# EFM_Power.net
KiCad netlist of a schematic drawn in Altium Designer
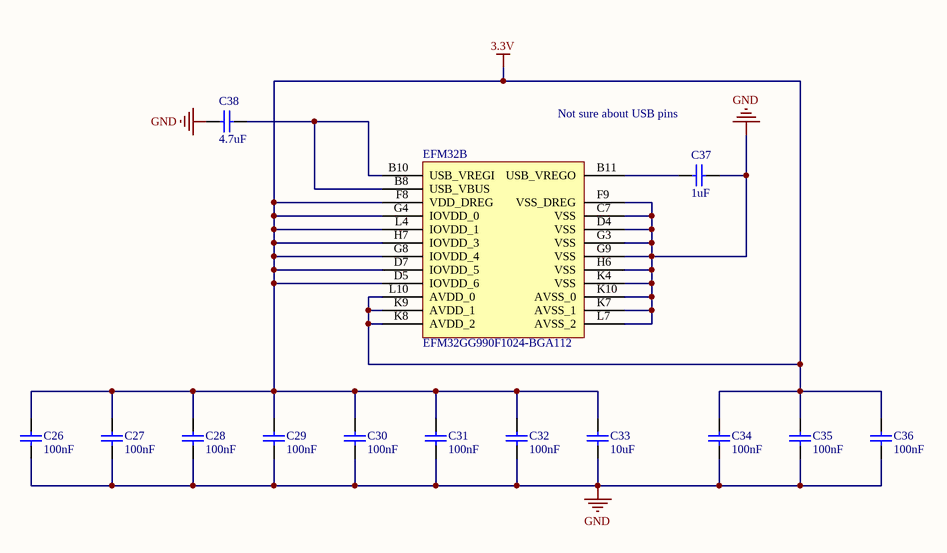
[diagram p0: EFM Power.SchDoc]

(export (version "E")
  (design (tool "Eeschema 10.0.6"))
  (components
    (comp (ref "C26")
      (value "100nF")
      (footprint "CAPC0603(1608)100_N")
      (description "CAP 0.5pF 10V Â±0.1pF 0603 (1608 Metric) Thickness 1mm SMD")
      (fields (field (name "TOLERANCE") "Â±0.1pF"))
      (libsource (lib "Altium Inc") (part "CMP-1035-00001-1"))
    )
    (comp (ref "C27")
      (value "100nF")
      (footprint "CAPC0603(1608)100_N")
      (description "CAP 0.5pF 10V Â±0.1pF 0603 (1608 Metric) Thickness 1mm SMD")
      (fields (field (name "TOLERANCE") "Â±0.1pF"))
      (libsource (lib "Altium Inc") (part "CMP-1035-00001-1"))
    )
    (comp (ref "C28")
      (value "100nF")
      (footprint "CAPC0603(1608)100_N")
      (description "CAP 0.5pF 10V Â±0.1pF 0603 (1608 Metric) Thickness 1mm SMD")
      (fields (field (name "TOLERANCE") "Â±0.1pF"))
      (libsource (lib "Altium Inc") (part "CMP-1035-00001-1"))
    )
    (comp (ref "C29")
      (value "100nF")
      (footprint "CAPC0603(1608)100_N")
      (description "CAP 0.5pF 10V Â±0.1pF 0603 (1608 Metric) Thickness 1mm SMD")
      (fields (field (name "TOLERANCE") "Â±0.1pF"))
      (libsource (lib "Altium Inc") (part "CMP-1035-00001-1"))
    )
    (comp (ref "C30")
      (value "100nF")
      (footprint "CAPC0603(1608)100_N")
      (description "CAP 0.5pF 10V Â±0.1pF 0603 (1608 Metric) Thickness 1mm SMD")
      (fields (field (name "TOLERANCE") "Â±0.1pF"))
      (libsource (lib "Altium Inc") (part "CMP-1035-00001-1"))
    )
    (comp (ref "C31")
      (value "100nF")
      (footprint "CAPC0603(1608)100_N")
      (description "CAP 0.5pF 10V Â±0.1pF 0603 (1608 Metric) Thickness 1mm SMD")
      (fields (field (name "TOLERANCE") "Â±0.1pF"))
      (libsource (lib "Altium Inc") (part "CMP-1035-00001-1"))
    )
    (comp (ref "C32")
      (value "100nF")
      (footprint "CAPC0603(1608)100_N")
      (description "CAP 0.5pF 10V Â±0.1pF 0603 (1608 Metric) Thickness 1mm SMD")
      (fields (field (name "TOLERANCE") "Â±0.1pF"))
      (libsource (lib "Altium Inc") (part "CMP-1035-00001-1"))
    )
    (comp (ref "C33")
      (value "10uF")
      (footprint "CAPC0603(1608)100_N")
      (description "CAP 0.5pF 10V Â±0.1pF 0603 (1608 Metric) Thickness 1mm SMD")
      (fields (field (name "TOLERANCE") "Â±0.1pF"))
      (libsource (lib "Altium Inc") (part "CMP-1035-00001-1"))
    )
    (comp (ref "C34")
      (value "100nF")
      (footprint "CAPC0603(1608)100_N")
      (description "CAP 0.5pF 10V Â±0.1pF 0603 (1608 Metric) Thickness 1mm SMD")
      (fields (field (name "TOLERANCE") "Â±0.1pF"))
      (libsource (lib "Altium Inc") (part "CMP-1035-00001-1"))
    )
    (comp (ref "C35")
      (value "100nF")
      (footprint "CAPC0603(1608)100_N")
      (description "CAP 0.5pF 10V Â±0.1pF 0603 (1608 Metric) Thickness 1mm SMD")
      (fields (field (name "TOLERANCE") "Â±0.1pF"))
      (libsource (lib "Altium Inc") (part "CMP-1035-00001-1"))
    )
    (comp (ref "C36")
      (value "100nF")
      (footprint "CAPC0603(1608)100_N")
      (description "CAP 0.5pF 10V Â±0.1pF 0603 (1608 Metric) Thickness 1mm SMD")
      (fields (field (name "TOLERANCE") "Â±0.1pF"))
      (libsource (lib "Altium Inc") (part "CMP-1035-00001-1"))
    )
    (comp (ref "C37")
      (value "1uF")
      (footprint "CAPC0603(1608)100_N")
      (description "CAP 0.5pF 10V Â±0.1pF 0603 (1608 Metric) Thickness 1mm SMD")
      (fields (field (name "TOLERANCE") "Â±0.1pF"))
      (libsource (lib "Altium Inc") (part "CMP-1035-00001-1"))
    )
    (comp (ref "C38")
      (value "4.7uF")
      (footprint "CAPC0603(1608)100_N")
      (description "CAP 0.5pF 10V Â±0.1pF 0603 (1608 Metric) Thickness 1mm SMD")
      (fields (field (name "TOLERANCE") "Â±0.1pF"))
      (libsource (lib "Altium Inc") (part "CMP-1035-00001-1"))
    )
    (comp (ref "EFM32")
      (value "EFM32GG990F1024-BGA112")
      (footprint "ENMR-BGA112")
      (fields (field (name "GENERIC PART NUMBER") "EFM32GG990"))
      (libsource (lib "Silicon Labs Energy Micro EFM32") (part "EFM32GG990F1024-BGA112"))
    )
  )
  (nets
    (net (code "1") (name "3.3V") (class "Default")
      (node (ref "C26") (pin "2") (pinfunction "2_2") (pintype "passive"))
      (node (ref "C27") (pin "2") (pinfunction "2_2") (pintype "passive"))
      (node (ref "C28") (pin "2") (pinfunction "2_2") (pintype "passive"))
      (node (ref "C29") (pin "2") (pinfunction "2_2") (pintype "passive"))
      (node (ref "C30") (pin "2") (pinfunction "2_2") (pintype "passive"))
      (node (ref "C31") (pin "2") (pinfunction "2_2") (pintype "passive"))
      (node (ref "C32") (pin "1") (pinfunction "1_1") (pintype "passive"))
      (node (ref "C33") (pin "1") (pinfunction "1_1") (pintype "passive"))
      (node (ref "C34") (pin "1") (pinfunction "1_1") (pintype "passive"))
      (node (ref "C35") (pin "1") (pinfunction "1_1") (pintype "passive"))
      (node (ref "C36") (pin "1") (pinfunction "1_1") (pintype "passive"))
      (node (ref "EFM32") (pin "D5") (pinfunction "IOVDD_6_D5") (pintype "power_in"))
      (node (ref "EFM32") (pin "D7") (pinfunction "IOVDD_5_D7") (pintype "power_in"))
      (node (ref "EFM32") (pin "F8") (pinfunction "VDD_DREG_F8") (pintype "power_in"))
      (node (ref "EFM32") (pin "G4") (pinfunction "IOVDD_0_G4") (pintype "power_in"))
      (node (ref "EFM32") (pin "G8") (pinfunction "IOVDD_4_G8") (pintype "power_in"))
      (node (ref "EFM32") (pin "H7") (pinfunction "IOVDD_3_H7") (pintype "power_in"))
      (node (ref "EFM32") (pin "K8") (pinfunction "AVDD_2_K8") (pintype "power_in"))
      (node (ref "EFM32") (pin "K9") (pinfunction "AVDD_1_K9") (pintype "power_in"))
      (node (ref "EFM32") (pin "L10") (pinfunction "AVDD_0_L10") (pintype "power_in"))
      (node (ref "EFM32") (pin "L4") (pinfunction "IOVDD_1_L4") (pintype "power_in"))
    )
    (net (code "2") (name "GND") (class "Default")
      (node (ref "C26") (pin "1") (pinfunction "1_1") (pintype "passive"))
      (node (ref "C27") (pin "1") (pinfunction "1_1") (pintype "passive"))
      (node (ref "C28") (pin "1") (pinfunction "1_1") (pintype "passive"))
      (node (ref "C29") (pin "1") (pinfunction "1_1") (pintype "passive"))
      (node (ref "C30") (pin "1") (pinfunction "1_1") (pintype "passive"))
      (node (ref "C31") (pin "1") (pinfunction "1_1") (pintype "passive"))
      (node (ref "C32") (pin "2") (pinfunction "2_2") (pintype "passive"))
      (node (ref "C33") (pin "2") (pinfunction "2_2") (pintype "passive"))
      (node (ref "C34") (pin "2") (pinfunction "2_2") (pintype "passive"))
      (node (ref "C35") (pin "2") (pinfunction "2_2") (pintype "passive"))
      (node (ref "C36") (pin "2") (pinfunction "2_2") (pintype "passive"))
      (node (ref "C37") (pin "2") (pinfunction "2_2") (pintype "passive"))
      (node (ref "C38") (pin "1") (pinfunction "1_1") (pintype "passive"))
      (node (ref "EFM32") (pin "C7") (pinfunction "VSS_C7") (pintype "power_in"))
      (node (ref "EFM32") (pin "D4") (pinfunction "VSS_D4") (pintype "power_in"))
      (node (ref "EFM32") (pin "F9") (pinfunction "VSS_DREG_F9") (pintype "power_in"))
      (node (ref "EFM32") (pin "G3") (pinfunction "VSS_G3") (pintype "power_in"))
      (node (ref "EFM32") (pin "G9") (pinfunction "VSS_G9") (pintype "power_in"))
      (node (ref "EFM32") (pin "H6") (pinfunction "VSS_H6") (pintype "power_in"))
      (node (ref "EFM32") (pin "K10") (pinfunction "AVSS_0_K10") (pintype "power_in"))
      (node (ref "EFM32") (pin "K4") (pinfunction "VSS_K4") (pintype "power_in"))
      (node (ref "EFM32") (pin "K7") (pinfunction "AVSS_1_K7") (pintype "power_in"))
      (node (ref "EFM32") (pin "L7") (pinfunction "AVSS_2_L7") (pintype "power_in"))
    )
    (net (code "3") (name "Net-(EFM32B-USB_VBUS)") (class "Default")
      (node (ref "C38") (pin "2") (pinfunction "2_2") (pintype "passive"))
      (node (ref "EFM32") (pin "B10") (pinfunction "USB_VREGI_B10") (pintype "power_in"))
      (node (ref "EFM32") (pin "B8") (pinfunction "USB_VBUS_B8") (pintype "power_in"))
    )
    (net (code "4") (name "Net-(EFM32B-USB_VREGO)") (class "Default")
      (node (ref "C37") (pin "1") (pinfunction "1_1") (pintype "passive"))
      (node (ref "EFM32") (pin "B11") (pinfunction "USB_VREGO_B11") (pintype "passive"))
    )
  )
)
